# MRCS-Buckeroo_V1_6.net
KiCad netlist of a schematic drawn in EAGLE
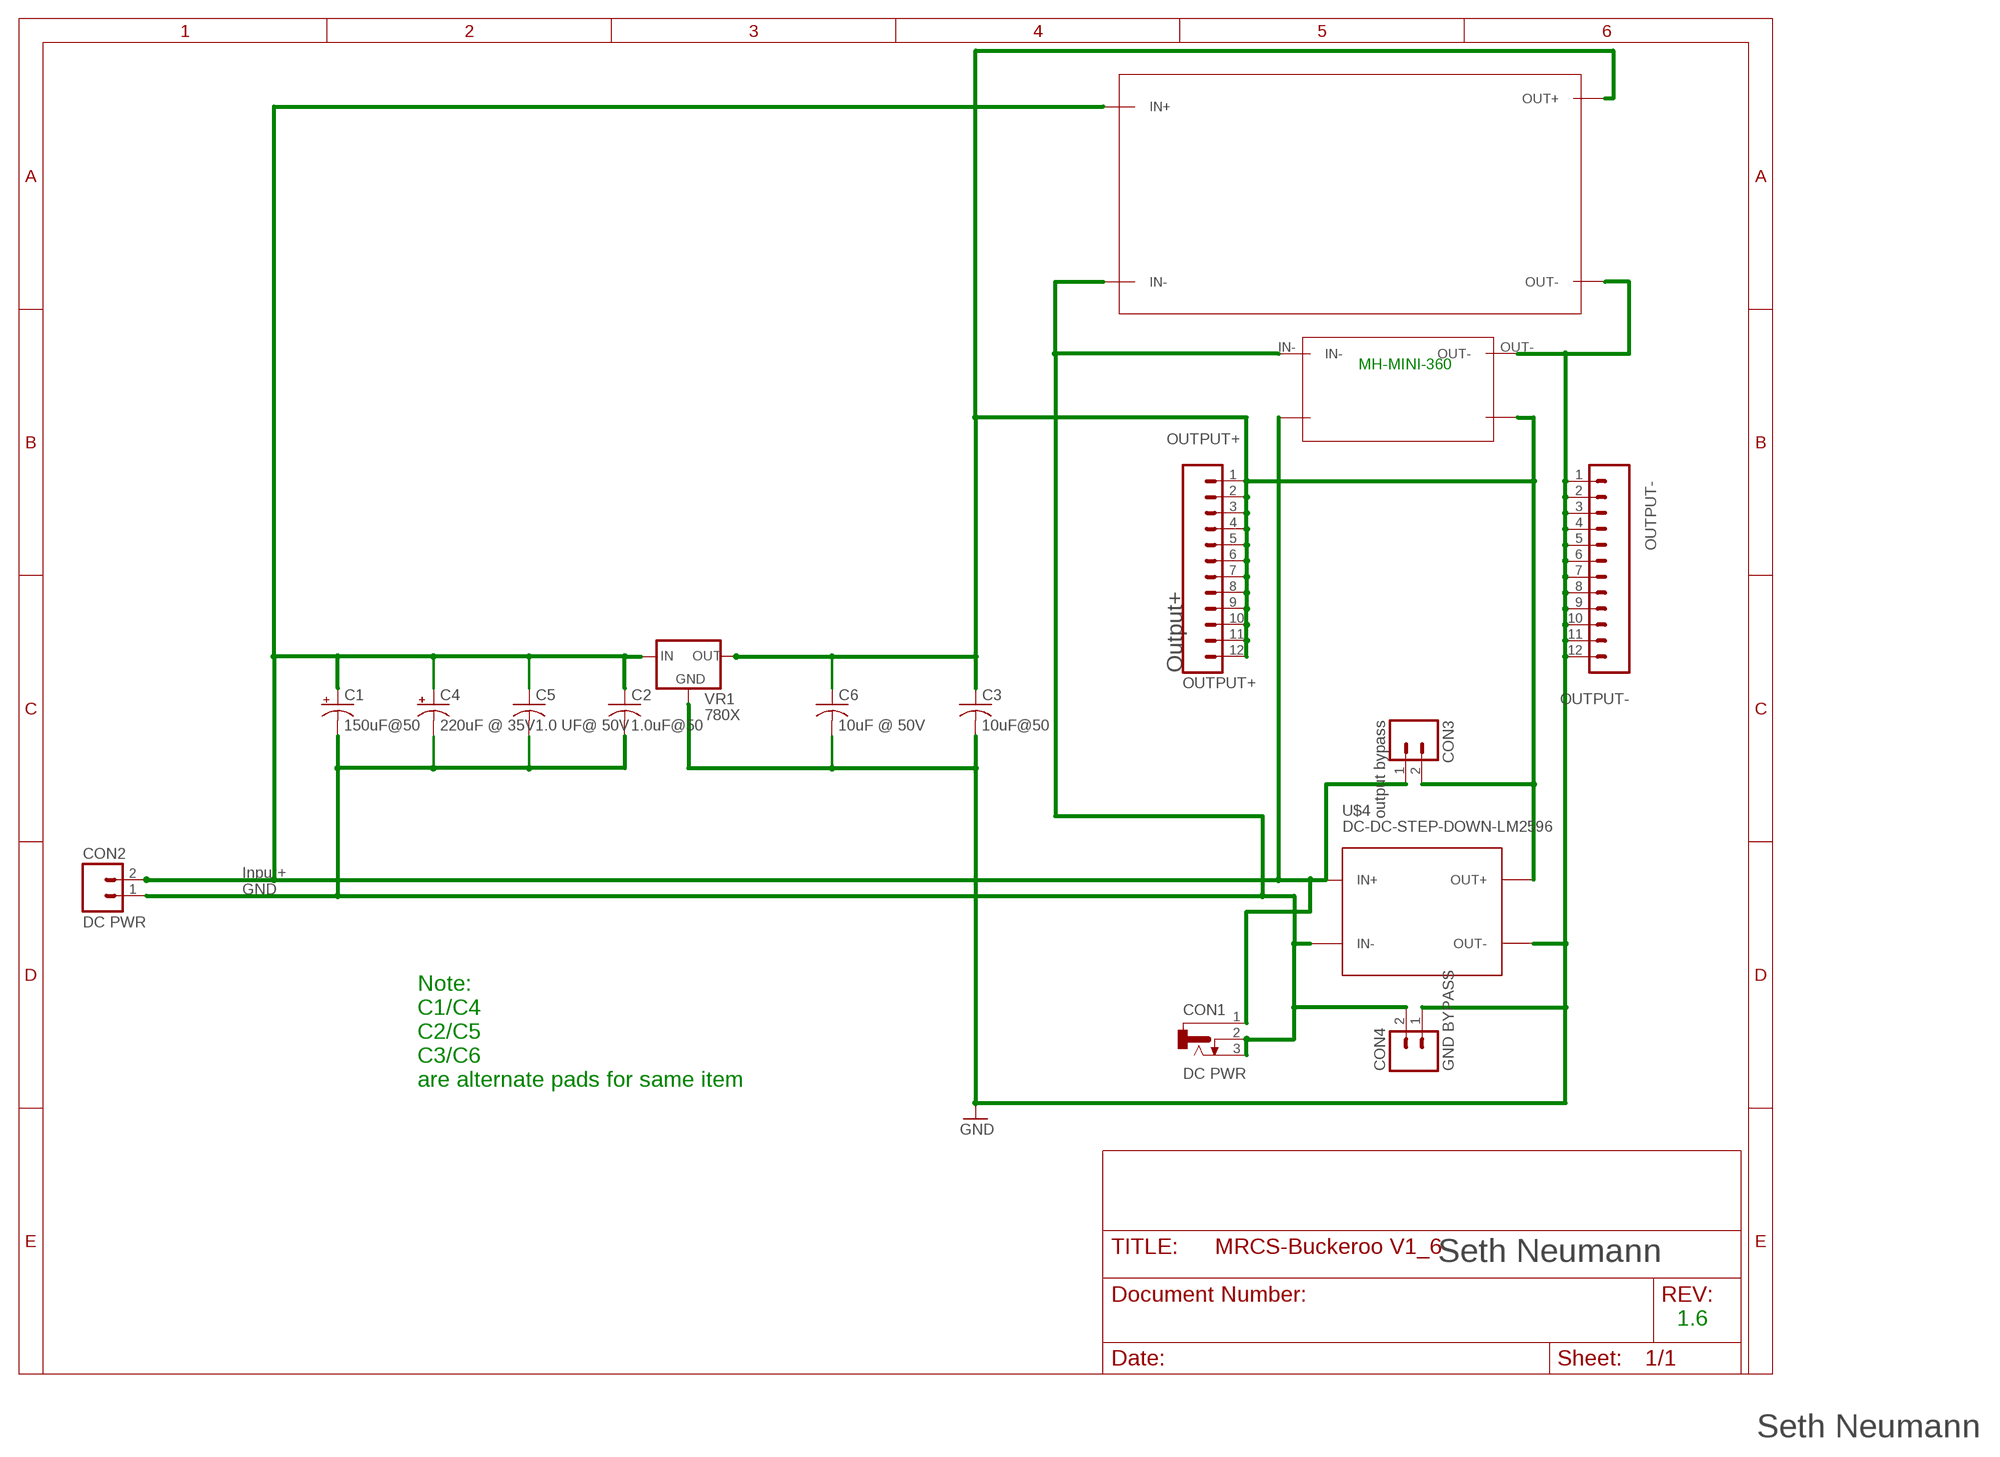
[diagram p0: schematic, sheet 1]

(export (version "E")
  (design (tool "Eeschema 10.0.6"))
  (components
    (comp (ref "C1")
      (value "150uF@50")
      (footprint "eagle-import:E5-10.5")
      (libsource (lib "eagle-import") (part "CAP-POLPTH-5MM"))
    )
    (comp (ref "C2")
      (value "1.0uF@50")
      (footprint "eagle-import:C-PTH-0.100")
      (libsource (lib "eagle-import") (part "CAPPTH2"))
    )
    (comp (ref "C3")
      (value "10uF@50")
      (footprint "eagle-import:C-PTH-0.100")
      (libsource (lib "eagle-import") (part "CAPPTH2"))
    )
    (comp (ref "C4")
      (value "220uF @ 35V")
      (footprint "eagle-import:E2.5-6")
      (libsource (lib "eagle-import") (part "CAP-POLPTH-2.5MM"))
    )
    (comp (ref "C5")
      (value "1.0 UF@ 50V")
      (footprint "eagle-import:C050-024X044")
      (libsource (lib "eagle-import") (part "CAPPTH1"))
    )
    (comp (ref "C6")
      (value "10uF @ 50V")
      (footprint "eagle-import:C050-024X044")
      (libsource (lib "eagle-import") (part "CAPPTH1"))
    )
    (comp (ref "CON1")
      (value "DC PWR")
      (footprint "eagle-import:DCJ0202")
      (libsource (lib "eagle-import") (part "CONNECTOR-DC-POWER-RA"))
    )
    (comp (ref "CON2")
      (value "DC PWR")
      (footprint "eagle-import:SCREWTERMINAL-3.5MM-2_LOCK")
      (libsource (lib "eagle-import") (part "CONNECTOR-M023.5MM-LOCK"))
    )
    (comp (ref "CON3")
      (value "output bypass")
      (footprint "eagle-import:MOLEX-1X2_LOCK")
      (libsource (lib "eagle-import") (part "CONNECTOR-M02MOLEX-1X02-LOCK"))
    )
    (comp (ref "CON4")
      (value "GND BYPASS")
      (footprint "eagle-import:MOLEX-1X2_LOCK")
      (libsource (lib "eagle-import") (part "CONNECTOR-M02MOLEX-1X02-LOCK"))
    )
    (comp (ref "MH-MINI-360")
      (value "MH-MINI-360")
      (footprint "eagle-import:MH-MINI-360")
      (libsource (lib "eagle-import") (part "MH-MINI-360"))
    )
    (comp (ref "OUTPUT+")
      (value "OUTPUT+")
      (footprint "eagle-import:1X12_LOCK")
      (libsource (lib "eagle-import") (part "CONNECTOR-M12LOCK"))
    )
    (comp (ref "OUTPUT-")
      (value "OUTPUT-")
      (footprint "eagle-import:1X12_LOCK")
      (libsource (lib "eagle-import") (part "CONNECTOR-M12LOCK"))
    )
    (comp (ref "U$4")
      (value "DC-DC-STEP-DOWN-LM2596")
      (footprint "eagle-import:DC-DC-STEP-DOWN-LM2596")
      (libsource (lib "eagle-import") (part "DC-DC-STEP-DOWN-LM2596"))
    )
    (comp (ref "U$5")
      (value "XL6009BOARD")
      (footprint "eagle-import:XL6009_BOARD")
      (libsource (lib "eagle-import") (part "XL6009BOARD"))
    )
    (comp (ref "VR1")
      (value "780X")
      (footprint "eagle-import:TO-220-RA")
      (libsource (lib "eagle-import") (part "VREG-?-PTH-RA"))
    )
  )
  (nets
    (net (code "1") (name "GND") (class "Default")
      (node (ref "C1") (pin "-") (pinfunction "-_-") (pintype "passive"))
      (node (ref "C2") (pin "2") (pinfunction "2_2") (pintype "passive"))
      (node (ref "C3") (pin "2") (pinfunction "2_2") (pintype "passive"))
      (node (ref "C4") (pin "-") (pinfunction "-_-") (pintype "passive"))
      (node (ref "C5") (pin "2") (pinfunction "2_2") (pintype "passive"))
      (node (ref "C6") (pin "2") (pinfunction "2_2") (pintype "passive"))
      (node (ref "CON1") (pin "2") (pinfunction "2_2") (pintype "passive"))
      (node (ref "CON1") (pin "3") (pinfunction "3_3") (pintype "passive"))
      (node (ref "CON2") (pin "1") (pinfunction "A_1") (pintype "passive"))
      (node (ref "CON4") (pin "1") (pinfunction "A_1") (pintype "passive"))
      (node (ref "CON4") (pin "2") (pinfunction "B_2") (pintype "passive"))
      (node (ref "MH-MINI-360") (pin "IN-") (pinfunction "IN-_IN-") (pintype "bidirectional"))
      (node (ref "MH-MINI-360") (pin "OUT-") (pinfunction "OUT-_OUT-") (pintype "bidirectional"))
      (node (ref "OUTPUT-") (pin "1") (pinfunction "1_1") (pintype "passive"))
      (node (ref "OUTPUT-") (pin "10") (pinfunction "10_10") (pintype "passive"))
      (node (ref "OUTPUT-") (pin "11") (pinfunction "11_11") (pintype "passive"))
      (node (ref "OUTPUT-") (pin "12") (pinfunction "12_12") (pintype "passive"))
      (node (ref "OUTPUT-") (pin "2") (pinfunction "2_2") (pintype "passive"))
      (node (ref "OUTPUT-") (pin "3") (pinfunction "3_3") (pintype "passive"))
      (node (ref "OUTPUT-") (pin "4") (pinfunction "4_4") (pintype "passive"))
      (node (ref "OUTPUT-") (pin "5") (pinfunction "5_5") (pintype "passive"))
      (node (ref "OUTPUT-") (pin "6") (pinfunction "6_6") (pintype "passive"))
      (node (ref "OUTPUT-") (pin "7") (pinfunction "7_7") (pintype "passive"))
      (node (ref "OUTPUT-") (pin "8") (pinfunction "8_8") (pintype "passive"))
      (node (ref "OUTPUT-") (pin "9") (pinfunction "9_9") (pintype "passive"))
      (node (ref "U$4") (pin "IN-") (pinfunction "IN-_IN-") (pintype "bidirectional"))
      (node (ref "U$4") (pin "OUT-") (pinfunction "OUT-_OUT-") (pintype "bidirectional"))
      (node (ref "U$5") (pin "IN-") (pinfunction "IN-_IN-") (pintype "bidirectional"))
      (node (ref "U$5") (pin "OUT-") (pinfunction "OUT-_OUT-") (pintype "bidirectional"))
      (node (ref "VR1") (pin "GND") (pinfunction "GND_GND") (pintype "input"))
    )
    (net (code "2") (name "Net-(CON2-B)") (class "Default")
      (node (ref "C1") (pin "+") (pinfunction "+_+") (pintype "passive"))
      (node (ref "C2") (pin "1") (pinfunction "1_1") (pintype "passive"))
      (node (ref "C4") (pin "+") (pinfunction "+_+") (pintype "passive"))
      (node (ref "C5") (pin "1") (pinfunction "1_1") (pintype "passive"))
      (node (ref "CON1") (pin "1") (pinfunction "1_1") (pintype "passive"))
      (node (ref "CON2") (pin "2") (pinfunction "B_2") (pintype "passive"))
      (node (ref "CON3") (pin "1") (pinfunction "A_1") (pintype "passive"))
      (node (ref "MH-MINI-360") (pin "INN+") (pinfunction "INN+_INN+") (pintype "bidirectional"))
      (node (ref "U$4") (pin "IN+") (pinfunction "IN+_IN+") (pintype "bidirectional"))
      (node (ref "U$5") (pin "IN+") (pinfunction "IN+_IN+") (pintype "bidirectional"))
      (node (ref "VR1") (pin "IN") (pinfunction "IN_IN") (pintype "input"))
    )
    (net (code "3") (name "Net-(CON3-B)") (class "Default")
      (node (ref "C3") (pin "1") (pinfunction "1_1") (pintype "passive"))
      (node (ref "C6") (pin "1") (pinfunction "1_1") (pintype "passive"))
      (node (ref "CON3") (pin "2") (pinfunction "B_2") (pintype "passive"))
      (node (ref "MH-MINI-360") (pin "OUTT+") (pinfunction "OUTT+_OUTT+") (pintype "bidirectional"))
      (node (ref "OUTPUT+") (pin "1") (pinfunction "1_1") (pintype "passive"))
      (node (ref "OUTPUT+") (pin "10") (pinfunction "10_10") (pintype "passive"))
      (node (ref "OUTPUT+") (pin "11") (pinfunction "11_11") (pintype "passive"))
      (node (ref "OUTPUT+") (pin "12") (pinfunction "12_12") (pintype "passive"))
      (node (ref "OUTPUT+") (pin "2") (pinfunction "2_2") (pintype "passive"))
      (node (ref "OUTPUT+") (pin "3") (pinfunction "3_3") (pintype "passive"))
      (node (ref "OUTPUT+") (pin "4") (pinfunction "4_4") (pintype "passive"))
      (node (ref "OUTPUT+") (pin "5") (pinfunction "5_5") (pintype "passive"))
      (node (ref "OUTPUT+") (pin "6") (pinfunction "6_6") (pintype "passive"))
      (node (ref "OUTPUT+") (pin "7") (pinfunction "7_7") (pintype "passive"))
      (node (ref "OUTPUT+") (pin "8") (pinfunction "8_8") (pintype "passive"))
      (node (ref "OUTPUT+") (pin "9") (pinfunction "9_9") (pintype "passive"))
      (node (ref "U$4") (pin "OUT+") (pinfunction "OUT+_OUT+") (pintype "bidirectional"))
      (node (ref "U$5") (pin "OUT+") (pinfunction "OUT+_OUT+") (pintype "bidirectional"))
      (node (ref "VR1") (pin "OUT") (pinfunction "OUT_OUT") (pintype "output"))
    )
  )
)
